# SNES_DRONE_ARTY_Z7.net
KiCad netlist of a schematic drawn in Altium Designer
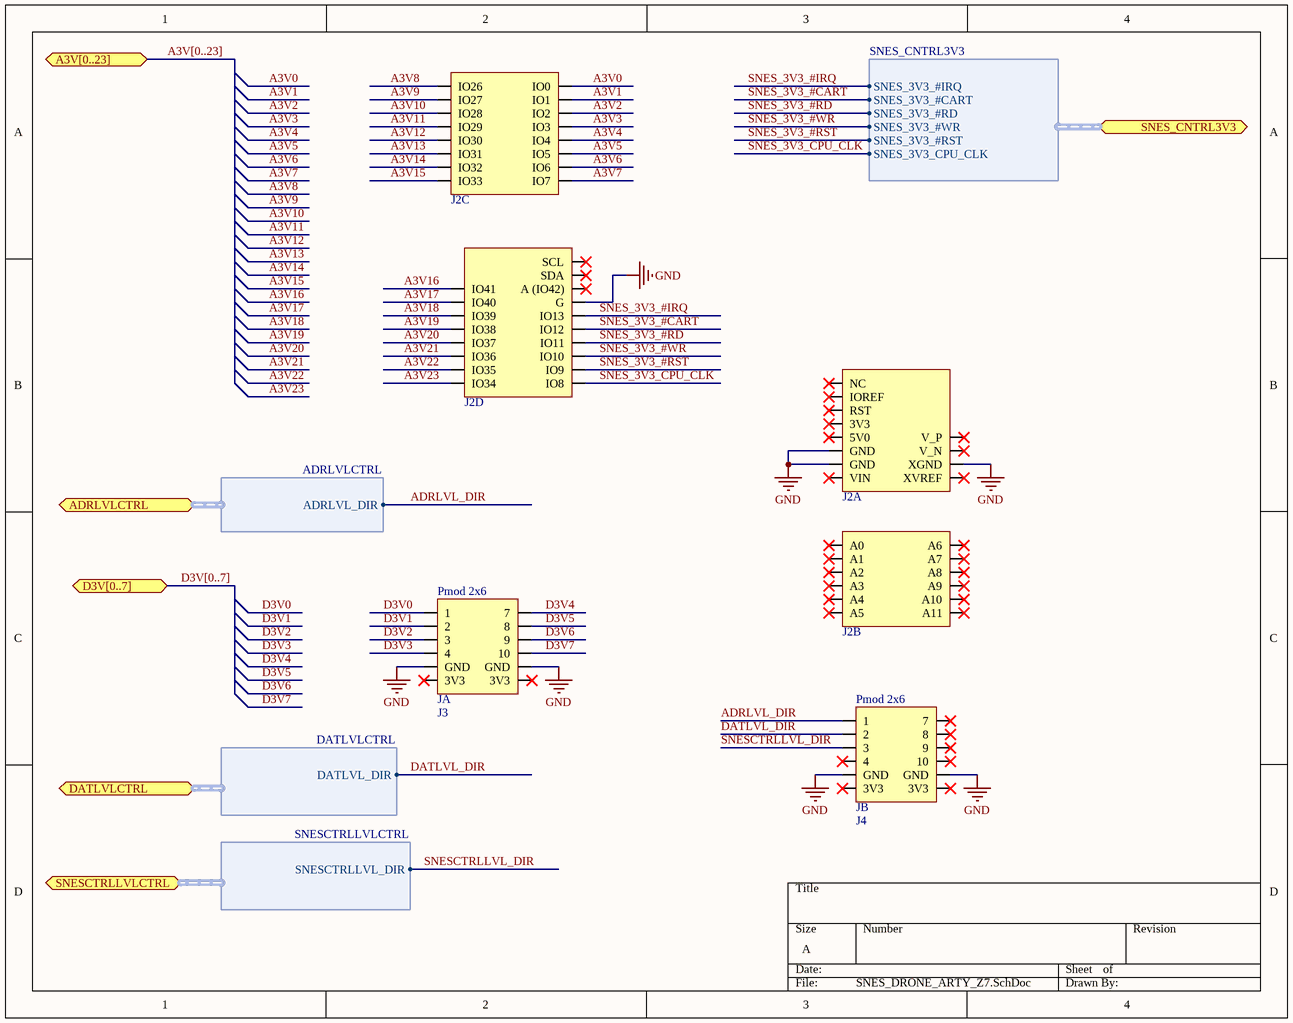
[diagram p0: SNES_DRONE_ARTY_Z7.SchDoc]

(export (version "E")
  (design (tool "Eeschema 10.0.6"))
  (components
    (comp (ref "J2")
      (value "ARTY_Z7")
      (footprint "arty-z7")
      (description "Connections to Arty Z7 SoC Board")
      (libsource (lib "mycomponents") (part "ARTY_Z7"))
    )
    (comp (ref "J3")
      (value "ARTY_Z7_PMOD_A")
      (footprint "arty-z7-pmod")
      (description "Connections to Arty Z7 SoC Board")
      (libsource (lib "mycomponents") (part "ARTY_Z7_PMOD_A"))
    )
    (comp (ref "J4")
      (value "ARTY_Z7_PMOD_B")
      (footprint "arty-z7-pmod")
      (description "Connections to Arty Z7 SoC Board")
      (libsource (lib "mycomponents") (part "ARTY_Z7_PMOD_B"))
    )
  )
  (nets
    (net (code "5") (name "/A3V0") (class "Default")
      (node (ref "J2") (pin "32") (pinfunction "IO0_32") (pintype "passive"))
    )
    (net (code "6") (name "/A3V1") (class "Default")
      (node (ref "J2") (pin "33") (pinfunction "IO1_33") (pintype "passive"))
    )
    (net (code "7") (name "/A3V2") (class "Default")
      (node (ref "J2") (pin "34") (pinfunction "IO2_34") (pintype "passive"))
    )
    (net (code "8") (name "/A3V3") (class "Default")
      (node (ref "J2") (pin "35") (pinfunction "IO3_35") (pintype "passive"))
    )
    (net (code "9") (name "/A3V4") (class "Default")
      (node (ref "J2") (pin "36") (pinfunction "IO4_36") (pintype "passive"))
    )
    (net (code "10") (name "/A3V5") (class "Default")
      (node (ref "J2") (pin "37") (pinfunction "IO5_37") (pintype "passive"))
    )
    (net (code "11") (name "/A3V6") (class "Default")
      (node (ref "J2") (pin "38") (pinfunction "IO6_38") (pintype "passive"))
    )
    (net (code "12") (name "/A3V7") (class "Default")
      (node (ref "J2") (pin "39") (pinfunction "IO7_39") (pintype "passive"))
    )
    (net (code "13") (name "/A3V8") (class "Default")
      (node (ref "J2") (pin "31") (pinfunction "IO26_31") (pintype "passive"))
    )
    (net (code "14") (name "/A3V9") (class "Default")
      (node (ref "J2") (pin "30") (pinfunction "IO27_30") (pintype "passive"))
    )
    (net (code "15") (name "/A3V10") (class "Default")
      (node (ref "J2") (pin "29") (pinfunction "IO28_29") (pintype "passive"))
    )
    (net (code "16") (name "/A3V11") (class "Default")
      (node (ref "J2") (pin "28") (pinfunction "IO29_28") (pintype "passive"))
    )
    (net (code "17") (name "/A3V12") (class "Default")
      (node (ref "J2") (pin "27") (pinfunction "IO30_27") (pintype "passive"))
    )
    (net (code "18") (name "/A3V13") (class "Default")
      (node (ref "J2") (pin "26") (pinfunction "IO31_26") (pintype "passive"))
    )
    (net (code "19") (name "/A3V14") (class "Default")
      (node (ref "J2") (pin "25") (pinfunction "IO32_25") (pintype "passive"))
    )
    (net (code "20") (name "/A3V15") (class "Default")
      (node (ref "J2") (pin "24") (pinfunction "IO33_24") (pintype "passive"))
    )
    (net (code "21") (name "/A3V16") (class "Default")
      (node (ref "J2") (pin "40") (pinfunction "IO41_40") (pintype "passive"))
    )
    (net (code "22") (name "/A3V17") (class "Default")
      (node (ref "J2") (pin "41") (pinfunction "IO40_41") (pintype "passive"))
    )
    (net (code "23") (name "/A3V18") (class "Default")
      (node (ref "J2") (pin "42") (pinfunction "IO39_42") (pintype "passive"))
    )
    (net (code "24") (name "/A3V19") (class "Default")
      (node (ref "J2") (pin "43") (pinfunction "IO38_43") (pintype "passive"))
    )
    (net (code "25") (name "/A3V20") (class "Default")
      (node (ref "J2") (pin "44") (pinfunction "IO37_44") (pintype "passive"))
    )
    (net (code "26") (name "/A3V21") (class "Default")
      (node (ref "J2") (pin "45") (pinfunction "IO36_45") (pintype "passive"))
    )
    (net (code "27") (name "/A3V22") (class "Default")
      (node (ref "J2") (pin "46") (pinfunction "IO35_46") (pintype "passive"))
    )
    (net (code "28") (name "/A3V23") (class "Default")
      (node (ref "J2") (pin "47") (pinfunction "IO34_47") (pintype "passive"))
    )
    (net (code "30") (name "/ADRLVL_DIR") (class "Default")
      (node (ref "J4") (pin "0") (pinfunction "1_0") (pintype "passive"))
    )
    (net (code "31") (name "/D3V0") (class "Default")
      (node (ref "J3") (pin "0") (pinfunction "1_0") (pintype "passive"))
    )
    (net (code "32") (name "/D3V1") (class "Default")
      (node (ref "J3") (pin "1") (pinfunction "2_1") (pintype "passive"))
    )
    (net (code "33") (name "/D3V2") (class "Default")
      (node (ref "J3") (pin "2") (pinfunction "3_2") (pintype "passive"))
    )
    (net (code "34") (name "/D3V3") (class "Default")
      (node (ref "J3") (pin "3") (pinfunction "4_3") (pintype "passive"))
    )
    (net (code "35") (name "/D3V4") (class "Default")
      (node (ref "J3") (pin "11") (pinfunction "7_11") (pintype "passive"))
    )
    (net (code "36") (name "/D3V5") (class "Default")
      (node (ref "J3") (pin "10") (pinfunction "8_10") (pintype "passive"))
    )
    (net (code "37") (name "/D3V6") (class "Default")
      (node (ref "J3") (pin "9") (pinfunction "9_9") (pintype "passive"))
    )
    (net (code "38") (name "/D3V7") (class "Default")
      (node (ref "J3") (pin "8") (pinfunction "10_8") (pintype "passive"))
    )
    (net (code "40") (name "/DATLVL_DIR") (class "Default")
      (node (ref "J4") (pin "1") (pinfunction "2_1") (pintype "passive"))
    )
    (net (code "41") (name "/SNESCTRLLVL_DIR") (class "Default")
      (node (ref "J4") (pin "2") (pinfunction "3_2") (pintype "passive"))
    )
    (net (code "42") (name "/SNES_3V3_#CART") (class "Default")
      (node (ref "J2") (pin "52") (pinfunction "IO12_52") (pintype "passive"))
    )
    (net (code "43") (name "/SNES_3V3_#IRQ") (class "Default")
      (node (ref "J2") (pin "53") (pinfunction "IO13_53") (pintype "passive"))
    )
    (net (code "44") (name "/SNES_3V3_#RD") (class "Default")
      (node (ref "J2") (pin "51") (pinfunction "IO11_51") (pintype "passive"))
    )
    (net (code "45") (name "/SNES_3V3_#RST") (class "Default")
      (node (ref "J2") (pin "49") (pinfunction "IO9_49") (pintype "passive"))
    )
    (net (code "46") (name "/SNES_3V3_#WR") (class "Default")
      (node (ref "J2") (pin "50") (pinfunction "IO10_50") (pintype "passive"))
    )
    (net (code "47") (name "/SNES_3V3_CPU_CLK") (class "Default")
      (node (ref "J2") (pin "48") (pinfunction "IO8_48") (pintype "passive"))
    )
    (net (code "52") (name "GND") (class "Default")
      (node (ref "J2") (pin "5") (pinfunction "GND_5") (pintype "passive"))
      (node (ref "J2") (pin "54") (pinfunction "G_54") (pintype "passive"))
      (node (ref "J2") (pin "6") (pinfunction "GND_6") (pintype "passive"))
      (node (ref "J2") (pin "9") (pinfunction "XGND_9") (pintype "passive"))
      (node (ref "J3") (pin "4") (pinfunction "GND_4") (pintype "passive"))
      (node (ref "J3") (pin "7") (pinfunction "GND_7") (pintype "passive"))
      (node (ref "J4") (pin "4") (pinfunction "GND_4") (pintype "passive"))
      (node (ref "J4") (pin "7") (pinfunction "GND_7") (pintype "passive"))
    )
    (net (code "53") (name "unconnected-(J2A-3V3-Pad3)") (class "Default")
      (node (ref "J2") (pin "3") (pinfunction "3V3_3") (pintype "passive+no_connect"))
    )
    (net (code "54") (name "unconnected-(J2A-5V0-Pad4)") (class "Default")
      (node (ref "J2") (pin "4") (pinfunction "5V0_4") (pintype "passive+no_connect"))
    )
    (net (code "55") (name "unconnected-(J2A-IOREF-Pad1)") (class "Default")
      (node (ref "J2") (pin "1") (pinfunction "IOREF_1") (pintype "passive+no_connect"))
    )
    (net (code "56") (name "unconnected-(J2A-NC-Pad0)") (class "Default")
      (node (ref "J2") (pin "0") (pinfunction "NC_0") (pintype "passive+no_connect"))
    )
    (net (code "57") (name "unconnected-(J2A-RST-Pad2)") (class "Default")
      (node (ref "J2") (pin "2") (pinfunction "RST_2") (pintype "passive+no_connect"))
    )
    (net (code "58") (name "unconnected-(J2A-VIN-Pad7)") (class "Default")
      (node (ref "J2") (pin "7") (pinfunction "VIN_7") (pintype "passive+no_connect"))
    )
    (net (code "59") (name "unconnected-(J2A-V_N-Pad10)") (class "Default")
      (node (ref "J2") (pin "10") (pinfunction "V_N_10") (pintype "passive+no_connect"))
    )
    (net (code "60") (name "unconnected-(J2A-V_P-Pad11)") (class "Default")
      (node (ref "J2") (pin "11") (pinfunction "V_P_11") (pintype "passive+no_connect"))
    )
    (net (code "61") (name "unconnected-(J2A-XVREF-Pad8)") (class "Default")
      (node (ref "J2") (pin "8") (pinfunction "XVREF_8") (pintype "passive+no_connect"))
    )
    (net (code "62") (name "unconnected-(J2B-A0-Pad12)") (class "Default")
      (node (ref "J2") (pin "12") (pinfunction "A0_12") (pintype "passive+no_connect"))
    )
    (net (code "63") (name "unconnected-(J2B-A1-Pad13)") (class "Default")
      (node (ref "J2") (pin "13") (pinfunction "A1_13") (pintype "passive+no_connect"))
    )
    (net (code "64") (name "unconnected-(J2B-A2-Pad14)") (class "Default")
      (node (ref "J2") (pin "14") (pinfunction "A2_14") (pintype "passive+no_connect"))
    )
    (net (code "65") (name "unconnected-(J2B-A3-Pad15)") (class "Default")
      (node (ref "J2") (pin "15") (pinfunction "A3_15") (pintype "passive+no_connect"))
    )
    (net (code "66") (name "unconnected-(J2B-A4-Pad16)") (class "Default")
      (node (ref "J2") (pin "16") (pinfunction "A4_16") (pintype "passive+no_connect"))
    )
    (net (code "67") (name "unconnected-(J2B-A5-Pad17)") (class "Default")
      (node (ref "J2") (pin "17") (pinfunction "A5_17") (pintype "passive+no_connect"))
    )
    (net (code "68") (name "unconnected-(J2B-A6-Pad23)") (class "Default")
      (node (ref "J2") (pin "23") (pinfunction "A6_23") (pintype "passive+no_connect"))
    )
    (net (code "69") (name "unconnected-(J2B-A7-Pad22)") (class "Default")
      (node (ref "J2") (pin "22") (pinfunction "A7_22") (pintype "passive+no_connect"))
    )
    (net (code "70") (name "unconnected-(J2B-A8-Pad21)") (class "Default")
      (node (ref "J2") (pin "21") (pinfunction "A8_21") (pintype "passive+no_connect"))
    )
    (net (code "71") (name "unconnected-(J2B-A9-Pad20)") (class "Default")
      (node (ref "J2") (pin "20") (pinfunction "A9_20") (pintype "passive+no_connect"))
    )
    (net (code "72") (name "unconnected-(J2B-A10-Pad19)") (class "Default")
      (node (ref "J2") (pin "19") (pinfunction "A10_19") (pintype "passive+no_connect"))
    )
    (net (code "73") (name "unconnected-(J2B-A11-Pad18)") (class "Default")
      (node (ref "J2") (pin "18") (pinfunction "A11_18") (pintype "passive+no_connect"))
    )
    (net (code "74") (name "unconnected-(J2D-A_(IO42)-Pad55)") (class "Default")
      (node (ref "J2") (pin "55") (pinfunction "A_(IO42)_55") (pintype "passive+no_connect"))
    )
    (net (code "75") (name "unconnected-(J2D-SCL-Pad57)") (class "Default")
      (node (ref "J2") (pin "57") (pinfunction "SCL_57") (pintype "passive+no_connect"))
    )
    (net (code "76") (name "unconnected-(J2D-SDA-Pad56)") (class "Default")
      (node (ref "J2") (pin "56") (pinfunction "SDA_56") (pintype "passive+no_connect"))
    )
    (net (code "77") (name "unconnected-(J3-3V3-Pad5)") (class "Default")
      (node (ref "J3") (pin "5") (pinfunction "3V3_5") (pintype "passive+no_connect"))
    )
    (net (code "78") (name "unconnected-(J3-3V3-Pad6)") (class "Default")
      (node (ref "J3") (pin "6") (pinfunction "3V3_6") (pintype "passive+no_connect"))
    )
    (net (code "79") (name "unconnected-(J4-3V3-Pad5)") (class "Default")
      (node (ref "J4") (pin "5") (pinfunction "3V3_5") (pintype "passive+no_connect"))
    )
    (net (code "80") (name "unconnected-(J4-3V3-Pad6)") (class "Default")
      (node (ref "J4") (pin "6") (pinfunction "3V3_6") (pintype "passive+no_connect"))
    )
    (net (code "81") (name "unconnected-(J4-4-Pad3)") (class "Default")
      (node (ref "J4") (pin "3") (pinfunction "4_3") (pintype "passive+no_connect"))
    )
    (net (code "82") (name "unconnected-(J4-7-Pad11)") (class "Default")
      (node (ref "J4") (pin "11") (pinfunction "7_11") (pintype "passive+no_connect"))
    )
    (net (code "83") (name "unconnected-(J4-8-Pad10)") (class "Default")
      (node (ref "J4") (pin "10") (pinfunction "8_10") (pintype "passive+no_connect"))
    )
    (net (code "84") (name "unconnected-(J4-10-Pad8)") (class "Default")
      (node (ref "J4") (pin "8") (pinfunction "10_8") (pintype "passive+no_connect"))
    )
    (net (code "85") (name "unconnected-(J4-Pad9)") (class "Default")
      (node (ref "J4") (pin "9") (pinfunction "9_9") (pintype "passive+no_connect"))
    )
  )
)
